# SH4_-_MICROCONTROLLER.net
KiCad netlist of a schematic drawn in Altium Designer
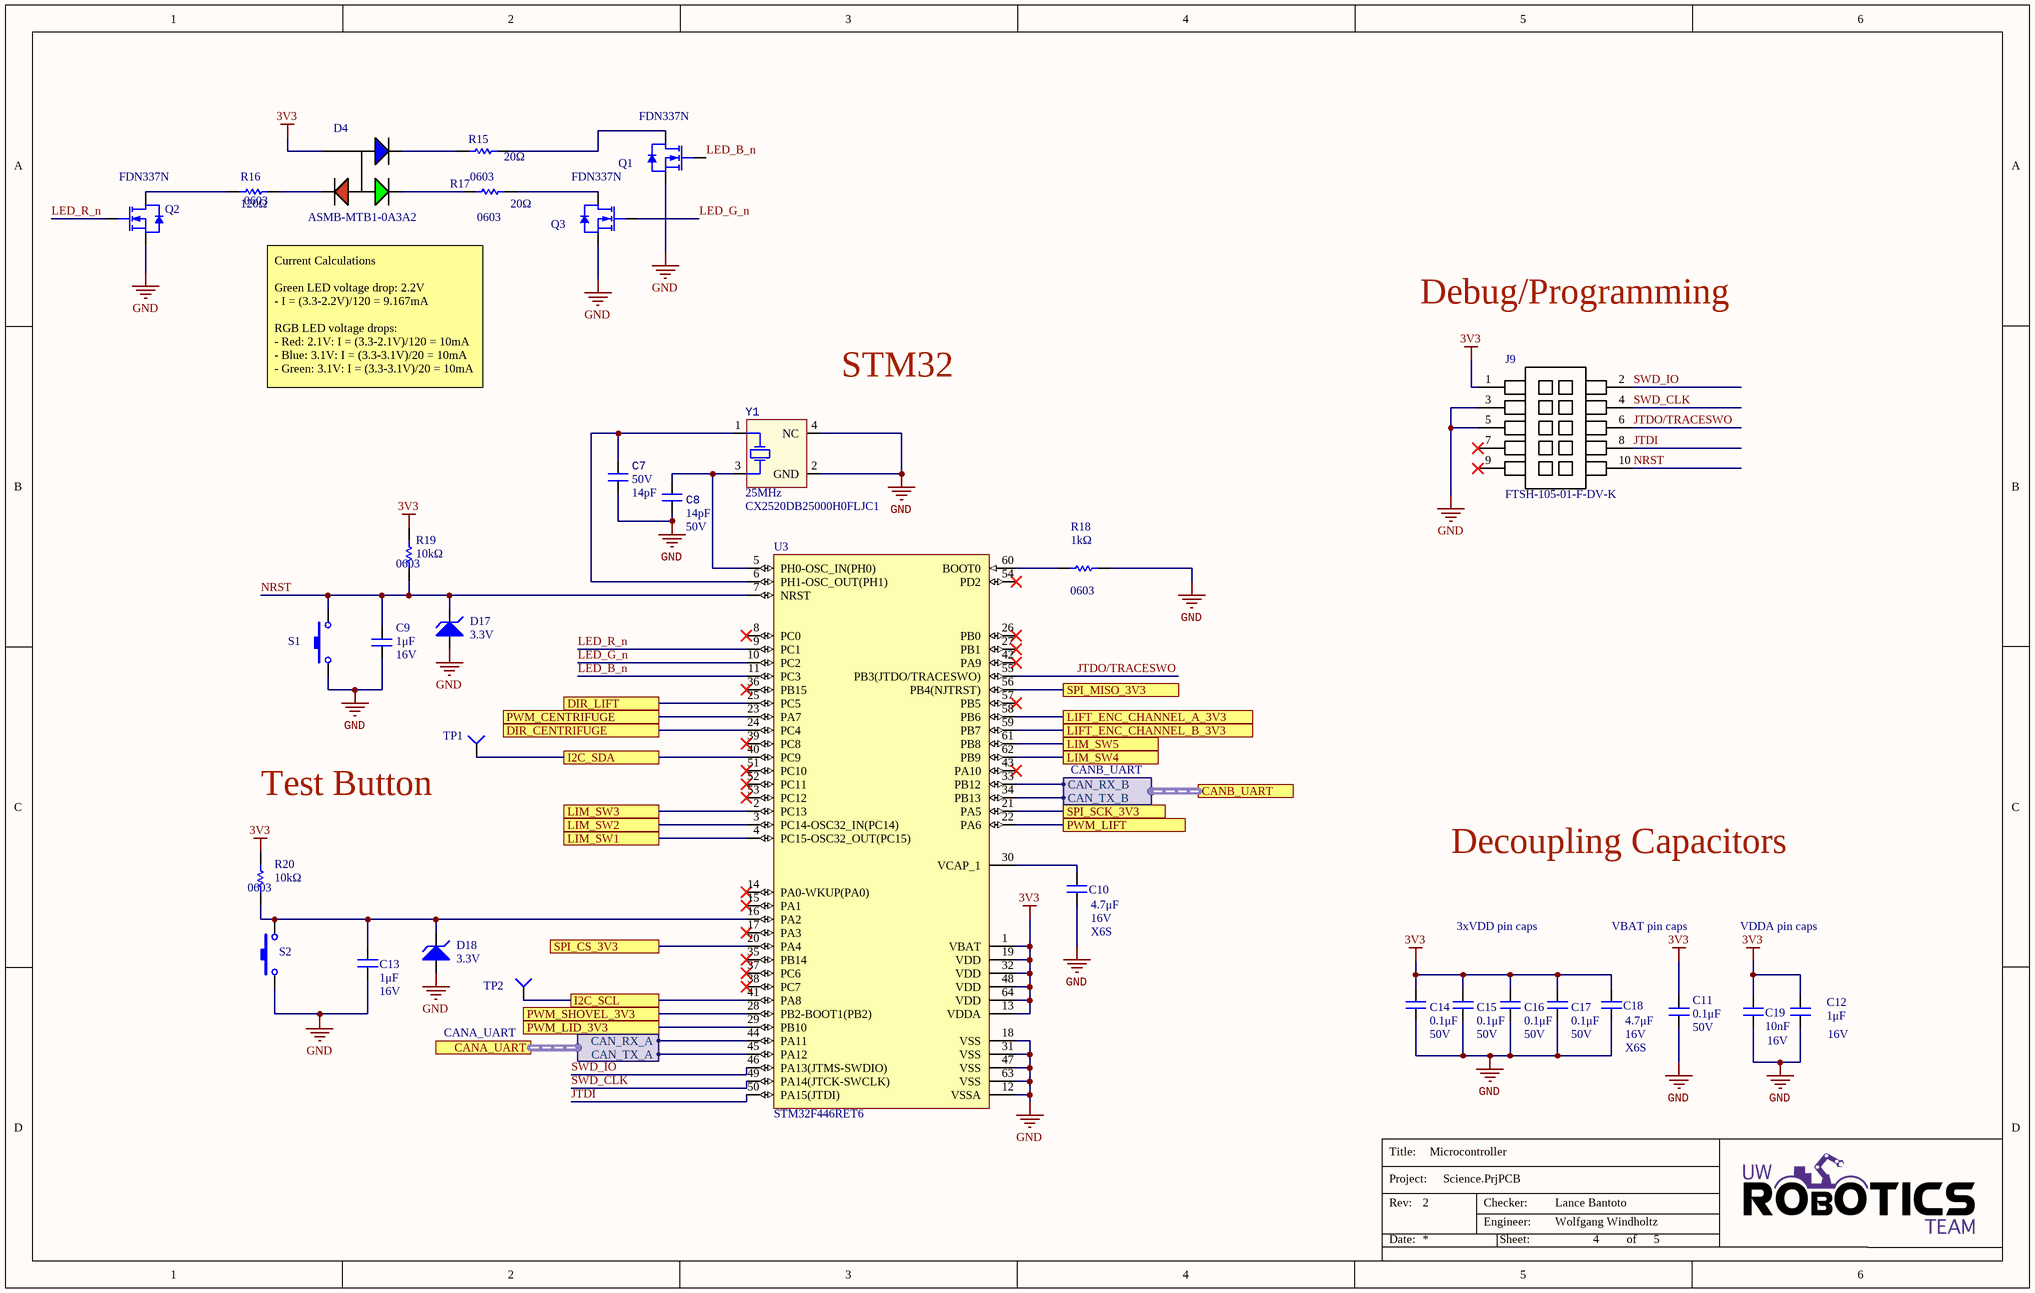
[diagram p0: SH4 - MICROCONTROLLER.SchDoc]

(export (version "E")
  (design (tool "Eeschema 10.0.6"))
  (components
    (comp (ref "C7")
      (value "14pF")
      (footprint "CAP0603")
      (description "CAP CER 14PF 50V C0G/NP0 0603")
      (fields (field (name "VOLTAGE RATING") "50V") (field (name "Comment") "CAP_14pF_50V_0603"))
      (libsource (lib "UWRT_Schematic_Library_2020") (part "CAP_14pF_50V_0603"))
    )
    (comp (ref "C8")
      (value "14pF")
      (footprint "CAP0603")
      (description "CAP CER 14PF 50V C0G/NP0 0603")
      (fields (field (name "VOLTAGE RATING") "50V") (field (name "Comment") "CAP_14pF_50V_0603"))
      (libsource (lib "UWRT_Schematic_Library_2020") (part "CAP_14pF_50V_0603"))
    )
    (comp (ref "C9")
      (value "1μF")
      (footprint "CAP0603")
      (description "CAP CER 1UF 16V Y5V 0603")
      (fields
        (field (name "VOLTAGE RATING") "16V")
        (field (name "MANUFACTURER PART NUMBER") "CC0603ZRY5V7BB105")
        (field (name "Comment") "CAP_1uF_16V_0603")
      )
      (libsource (lib "UWRT_Schematic_Library_2020") (part "CAP_1uF_16V_0603"))
    )
    (comp (ref "C10")
      (value "4.7μF")
      (footprint "CAP0603")
      (description "CAP CER 4.7UF 16V X6S 0603")
      (fields
        (field (name "DIELECTRIC") "X6S")
        (field (name "VOLTAGE RATING") "16V")
        (field (name "Comment") "CAP_4.7uF_16V_0603")
      )
      (libsource (lib "UWRT_Schematic_Library_2020") (part "CAP_4.7uF_16V_0603"))
    )
    (comp (ref "C11")
      (value "0.1μF")
      (footprint "CAP0603")
      (description "CAP CER 0.1UF 50V X7R 0603")
      (fields (field (name "VOLTAGE RATING") "50V") (field (name "Comment") "CAP_0.1uF_50V_0603"))
      (libsource (lib "UWRT_Schematic_Library_2020") (part "CAP_0.1uF_50V_0603"))
    )
    (comp (ref "C12")
      (value "1μF")
      (footprint "CAP0603")
      (description "CAP CER 1UF 16V Y5V 0603")
      (fields
        (field (name "VOLTAGE RATING") "16V")
        (field (name "MANUFACTURER PART NUMBER") "CC0603ZRY5V7BB105")
        (field (name "Comment") "CAP_1uF_16V_0603")
      )
      (libsource (lib "UWRT_Schematic_Library_2020") (part "CAP_1uF_16V_0603"))
    )
    (comp (ref "C13")
      (value "1μF")
      (footprint "CAP0603")
      (description "CAP CER 1UF 16V Y5V 0603")
      (fields
        (field (name "VOLTAGE RATING") "16V")
        (field (name "MANUFACTURER PART NUMBER") "CC0603ZRY5V7BB105")
        (field (name "Comment") "CAP_1uF_16V_0603")
      )
      (libsource (lib "UWRT_Schematic_Library_2020") (part "CAP_1uF_16V_0603"))
    )
    (comp (ref "C14")
      (value "0.1μF")
      (footprint "CAP0603")
      (description "CAP CER 0.1UF 50V X7R 0603")
      (fields (field (name "VOLTAGE RATING") "50V") (field (name "Comment") "CAP_0.1uF_50V_0603"))
      (libsource (lib "UWRT_Schematic_Library_2020") (part "CAP_0.1uF_50V_0603"))
    )
    (comp (ref "C15")
      (value "0.1μF")
      (footprint "CAP0603")
      (description "CAP CER 0.1UF 50V X7R 0603")
      (fields (field (name "VOLTAGE RATING") "50V") (field (name "Comment") "CAP_0.1uF_50V_0603"))
      (libsource (lib "UWRT_Schematic_Library_2020") (part "CAP_0.1uF_50V_0603"))
    )
    (comp (ref "C16")
      (value "0.1μF")
      (footprint "CAP0603")
      (description "CAP CER 0.1UF 50V X7R 0603")
      (fields (field (name "VOLTAGE RATING") "50V") (field (name "Comment") "CAP_0.1uF_50V_0603"))
      (libsource (lib "UWRT_Schematic_Library_2020") (part "CAP_0.1uF_50V_0603"))
    )
    (comp (ref "C17")
      (value "0.1μF")
      (footprint "CAP0603")
      (description "CAP CER 0.1UF 50V X7R 0603")
      (fields (field (name "VOLTAGE RATING") "50V") (field (name "Comment") "CAP_0.1uF_50V_0603"))
      (libsource (lib "UWRT_Schematic_Library_2020") (part "CAP_0.1uF_50V_0603"))
    )
    (comp (ref "C18")
      (value "4.7μF")
      (footprint "CAP0603")
      (description "CAP CER 4.7UF 16V X6S 0603")
      (fields
        (field (name "DIELECTRIC") "X6S")
        (field (name "VOLTAGE RATING") "16V")
        (field (name "Comment") "CAP_4.7uF_16V_0603")
      )
      (libsource (lib "UWRT_Schematic_Library_2020") (part "CAP_4.7uF_16V_0603"))
    )
    (comp (ref "C19")
      (value "10nF")
      (footprint "CAP0603")
      (description "CAP CER 10000PF 16V X7R 0603")
      (fields (field (name "VOLTAGE RATING") "16V") (field (name "Comment") "CAP_10nF_0603"))
      (libsource (lib "UWRT_Schematic_Library_2020") (part "CAP_10nF_0603"))
    )
    (comp (ref "D4")
      (value "LED_RGB")
      (footprint "LED_RGB")
      (description "LED RGB DIFFUSED 4PLCC SMD")
      (fields (field (name "MANUFACTURER PART NUMBER 1") "ASMB-MTB1-0A3A2"))
      (libsource (lib "UWRT_Schematic_Library_2020") (part "LED_RGB"))
    )
    (comp (ref "D17")
      (value "ESD5Z3.3T1G")
      (footprint "SOD523_UNI")
      (description "TVS DIODE 3.3V 14.1V SOD523")
      (fields (field (name "REVERSE STANDOFF VOLTAGE") "3.3V"))
      (libsource (lib "UWRT_Schematic_Library_2020") (part "ESD5Z3.3T1G"))
    )
    (comp (ref "D18")
      (value "ESD5Z3.3T1G")
      (footprint "SOD523_UNI")
      (description "TVS DIODE 3.3V 14.1V SOD523")
      (fields (field (name "REVERSE STANDOFF VOLTAGE") "3.3V"))
      (libsource (lib "UWRT_Schematic_Library_2020") (part "ESD5Z3.3T1G"))
    )
    (comp (ref "J9")
      (value "CON_PROGRAMMING")
      (footprint "FTSH-105-01-F-DV-K-P-TR")
      (description "CONN HEADER SMD 10POS 1.27MM")
      (fields (field (name "MANUFACTURER PART NUMBER 1") "FTSH-105-01-F-DV-K"))
      (libsource (lib "UWRT_Schematic_Library_2020") (part "CON_PROGRAMMING"))
    )
    (comp (ref "Q1")
      (value "NMOS_30V_2.2A")
      (footprint "NMOS_SSOT-3")
      (description "MOSFET N-CH 30V 2.2A SUPERSOT3")
      (fields (field (name "MANUFACTURER PART NUMBER 1") "FDN337N"))
      (libsource (lib "UWRT_Schematic_Library_2020") (part "NMOS_30V_2.2A"))
    )
    (comp (ref "Q2")
      (value "NMOS_30V_2.2A")
      (footprint "NMOS_SSOT-3")
      (description "MOSFET N-CH 30V 2.2A SUPERSOT3")
      (fields (field (name "MANUFACTURER PART NUMBER 1") "FDN337N"))
      (libsource (lib "UWRT_Schematic_Library_2020") (part "NMOS_30V_2.2A"))
    )
    (comp (ref "Q3")
      (value "NMOS_30V_2.2A")
      (footprint "NMOS_SSOT-3")
      (description "MOSFET N-CH 30V 2.2A SUPERSOT3")
      (fields (field (name "MANUFACTURER PART NUMBER 1") "FDN337N"))
      (libsource (lib "UWRT_Schematic_Library_2020") (part "NMOS_30V_2.2A"))
    )
    (comp (ref "R15")
      (value "20Ω")
      (footprint "RESC0603")
      (description "RES 20 OHM 5% 1/10W 0603")
      (fields
        (field (name "TOLERANCE") "5%")
        (field (name "PACKAGE/FOOTPRINT") "0603")
        (field (name "Comment") "RES_20Ω_0603_5%")
      )
      (libsource (lib "UWRT_Schematic_Library_2020") (part "RES_20Ω_0603_5%"))
    )
    (comp (ref "R16")
      (value "120Ω")
      (footprint "RESC0603")
      (description "RES 120 OHM 5% 1/10W 0603")
      (fields (field (name "PACKAGE/FOOTPRINT") "0603") (field (name "Comment") "RES_120Ω_0603"))
      (libsource (lib "UWRT_Schematic_Library_2020") (part "RES_120Ω_0603_5%"))
    )
    (comp (ref "R17")
      (value "20Ω")
      (footprint "RESC0603")
      (description "RES 20 OHM 5% 1/10W 0603")
      (fields
        (field (name "TOLERANCE") "5%")
        (field (name "PACKAGE/FOOTPRINT") "0603")
        (field (name "Comment") "RES_20Ω_0603_5%")
      )
      (libsource (lib "UWRT_Schematic_Library_2020") (part "RES_20Ω_0603_5%"))
    )
    (comp (ref "R18")
      (value "1kΩ")
      (footprint "RESC0603")
      (description "RES 1K OHM 5% 1/10W 0603")
      (fields
        (field (name "TOLERANCE") "5%")
        (field (name "PACKAGE/FOOTPRINT") "0603")
        (field (name "Comment") "RES_1kΩ_0603_5%")
      )
      (libsource (lib "UWRT_Schematic_Library_2020") (part "RES_1kΩ_0603_5%"))
    )
    (comp (ref "R19")
      (value "10kΩ")
      (footprint "RESC0603")
      (description "RES 10K OHM 5% 1/10W 0603")
      (fields
        (field (name "TOLERANCE") "5%")
        (field (name "PACKAGE/FOOTPRINT") "0603")
        (field (name "Comment") "RES_10kΩ_0603_5%")
      )
      (libsource (lib "UWRT_Schematic_Library_2020") (part "RES_10kΩ_0603_5%"))
    )
    (comp (ref "R20")
      (value "10kΩ")
      (footprint "RESC0603")
      (description "RES 10K OHM 5% 1/10W 0603")
      (fields
        (field (name "TOLERANCE") "5%")
        (field (name "PACKAGE/FOOTPRINT") "0603")
        (field (name "Comment") "RES_10kΩ_0603_5%")
      )
      (libsource (lib "UWRT_Schematic_Library_2020") (part "RES_10kΩ_0603_5%"))
    )
    (comp (ref "S1")
      (value "SW_TACTILE")
      (footprint "B3U-1000P")
      (description "SWITCH TACTILE SPST-NO 0.05A 12V")
      (libsource (lib "UWRT_Schematic_Library_2020") (part "SW_TACTILE"))
    )
    (comp (ref "S2")
      (value "SW_TACTILE")
      (footprint "B3U-1000P")
      (description "SWITCH TACTILE SPST-NO 0.05A 12V")
      (libsource (lib "UWRT_Schematic_Library_2020") (part "SW_TACTILE"))
    )
    (comp (ref "TP1")
      (value "TESTPOINT_1MM_CIRCLE")
      (footprint "TESTPOINT_CIRCLE_1MM")
      (description "TESTPOINT 1MM CIRCLE")
      (libsource (lib "UWRT_Schematic_Library_2020") (part "TESTPOINT_1MM_CIRCLE"))
    )
    (comp (ref "TP2")
      (value "TESTPOINT_1MM_CIRCLE")
      (footprint "TESTPOINT_CIRCLE_1MM")
      (description "TESTPOINT 1MM CIRCLE")
      (libsource (lib "UWRT_Schematic_Library_2020") (part "TESTPOINT_1MM_CIRCLE"))
    )
    (comp (ref "U3")
      (value "STM32F446RET6")
      (footprint "STM-LQFP64_L")
      (libsource (lib "UWRT_Schematic_Library_2020") (part "MCU_STM32F446RET6"))
    )
    (comp (ref "Y1")
      (value "CRYSTAL_25MHZ")
      (footprint "SOIC254P1016X440-4N")
      (description "CRYSTAL 25.0000MHZ 12PF SMD")
      (fields
        (field (name "FREQUENCY") "25MHz")
        (field (name "MANUFACTURER PART NUMBER 1") "CX2520DB25000H0FLJC1")
      )
      (libsource (lib "UWRT_Schematic_Library_2020") (part "CRYSTAL_25MHZ"))
    )
  )
  (nets
    (net (code "3") (name "/CAN_RX_A") (class "Default")
      (node (ref "U3") (pin "44") (pinfunction "PA11_44") (pintype "bidirectional"))
    )
    (net (code "4") (name "/CAN_RX_B") (class "Default")
      (node (ref "U3") (pin "33") (pinfunction "PB12_33") (pintype "bidirectional"))
    )
    (net (code "5") (name "/CAN_TX_A") (class "Default")
      (node (ref "U3") (pin "45") (pinfunction "PA12_45") (pintype "bidirectional"))
    )
    (net (code "6") (name "/CAN_TX_B") (class "Default")
      (node (ref "U3") (pin "34") (pinfunction "PB13_34") (pintype "bidirectional"))
    )
    (net (code "7") (name "/DIR_CENTRIFUGE") (class "Default")
      (node (ref "U3") (pin "24") (pinfunction "PC4_24") (pintype "bidirectional"))
    )
    (net (code "8") (name "/DIR_LIFT") (class "Default")
      (node (ref "U3") (pin "25") (pinfunction "PC5_25") (pintype "bidirectional"))
    )
    (net (code "9") (name "/I2C_SCL") (class "Default")
      (node (ref "TP2") (pin "1") (pinfunction "=value_1") (pintype "passive"))
      (node (ref "U3") (pin "41") (pinfunction "PA8_41") (pintype "bidirectional"))
    )
    (net (code "10") (name "/I2C_SDA") (class "Default")
      (node (ref "TP1") (pin "1") (pinfunction "=value_1") (pintype "passive"))
      (node (ref "U3") (pin "40") (pinfunction "PC9_40") (pintype "bidirectional"))
    )
    (net (code "11") (name "/JTDI") (class "Default")
      (node (ref "J9") (pin "8") (pinfunction "8_8") (pintype "passive"))
      (node (ref "U3") (pin "50") (pinfunction "PA15(JTDI)_50") (pintype "bidirectional"))
    )
    (net (code "12") (name "/JTDO{slash}TRACESWO") (class "Default")
      (node (ref "J9") (pin "6") (pinfunction "6_6") (pintype "passive"))
      (node (ref "U3") (pin "55") (pinfunction "PB3(JTDO/TRACESWO)_55") (pintype "bidirectional"))
    )
    (net (code "13") (name "/LED_B_n") (class "Default")
      (node (ref "Q1") (pin "1") (pinfunction "GATE_1") (pintype "passive"))
      (node (ref "U3") (pin "11") (pinfunction "PC3_11") (pintype "bidirectional"))
    )
    (net (code "14") (name "/LED_G_n") (class "Default")
      (node (ref "Q3") (pin "1") (pinfunction "GATE_1") (pintype "passive"))
      (node (ref "U3") (pin "10") (pinfunction "PC2_10") (pintype "bidirectional"))
    )
    (net (code "15") (name "/LED_R_n") (class "Default")
      (node (ref "Q2") (pin "1") (pinfunction "GATE_1") (pintype "passive"))
      (node (ref "U3") (pin "9") (pinfunction "PC1_9") (pintype "bidirectional"))
    )
    (net (code "16") (name "/LIFT_ENC_CHANNEL_A_3V3") (class "Default")
      (node (ref "U3") (pin "58") (pinfunction "PB6_58") (pintype "bidirectional"))
    )
    (net (code "17") (name "/LIFT_ENC_CHANNEL_B_3V3") (class "Default")
      (node (ref "U3") (pin "59") (pinfunction "PB7_59") (pintype "bidirectional"))
    )
    (net (code "18") (name "/LIM_SW1") (class "Default")
      (node (ref "U3") (pin "4") (pinfunction "PC15-OSC32_OUT(PC15)_4") (pintype "bidirectional"))
    )
    (net (code "19") (name "/LIM_SW2") (class "Default")
      (node (ref "U3") (pin "3") (pinfunction "PC14-OSC32_IN(PC14)_3") (pintype "bidirectional"))
    )
    (net (code "20") (name "/LIM_SW3") (class "Default")
      (node (ref "U3") (pin "2") (pinfunction "PC13_2") (pintype "bidirectional"))
    )
    (net (code "21") (name "/LIM_SW4") (class "Default")
      (node (ref "U3") (pin "62") (pinfunction "PB9_62") (pintype "bidirectional"))
    )
    (net (code "22") (name "/LIM_SW5") (class "Default")
      (node (ref "U3") (pin "61") (pinfunction "PB8_61") (pintype "bidirectional"))
    )
    (net (code "23") (name "/NRST") (class "Default")
      (node (ref "C9") (pin "2") (pinfunction "2_2") (pintype "passive"))
      (node (ref "D17") (pin "2") (pinfunction "Cathode_2") (pintype "passive"))
      (node (ref "J9") (pin "10") (pinfunction "10_10") (pintype "passive"))
      (node (ref "R19") (pin "1") (pinfunction "1_1") (pintype "passive"))
      (node (ref "S1") (pin "1") (pinfunction "1_1") (pintype "passive"))
      (node (ref "U3") (pin "7") (pinfunction "NRST_7") (pintype "bidirectional"))
    )
    (net (code "24") (name "/PWM_CENTRIFUGE") (class "Default")
      (node (ref "U3") (pin "23") (pinfunction "PA7_23") (pintype "bidirectional"))
    )
    (net (code "25") (name "/PWM_LID_3V3") (class "Default")
      (node (ref "U3") (pin "29") (pinfunction "PB10_29") (pintype "bidirectional"))
    )
    (net (code "26") (name "/PWM_LIFT") (class "Default")
      (node (ref "U3") (pin "22") (pinfunction "PA6_22") (pintype "bidirectional"))
    )
    (net (code "27") (name "/PWM_SHOVEL_3V3") (class "Default")
      (node (ref "U3") (pin "28") (pinfunction "PB2-BOOT1(PB2)_28") (pintype "bidirectional"))
    )
    (net (code "28") (name "/SPI_CS_3V3") (class "Default")
      (node (ref "U3") (pin "20") (pinfunction "PA4_20") (pintype "bidirectional"))
    )
    (net (code "29") (name "/SPI_MISO_3V3") (class "Default")
      (node (ref "U3") (pin "56") (pinfunction "PB4(NJTRST)_56") (pintype "bidirectional"))
    )
    (net (code "30") (name "/SPI_SCK_3V3") (class "Default")
      (node (ref "U3") (pin "21") (pinfunction "PA5_21") (pintype "bidirectional"))
    )
    (net (code "31") (name "/SWD_CLK") (class "Default")
      (node (ref "J9") (pin "4") (pinfunction "4_4") (pintype "passive"))
      (node (ref "U3") (pin "49") (pinfunction "PA14(JTCK-SWCLK)_49") (pintype "bidirectional"))
    )
    (net (code "32") (name "/SWD_IO") (class "Default")
      (node (ref "J9") (pin "2") (pinfunction "2_2") (pintype "passive"))
      (node (ref "U3") (pin "46") (pinfunction "PA13(JTMS-SWDIO)_46") (pintype "bidirectional"))
    )
    (net (code "35") (name "3V3") (class "Default")
      (node (ref "C11") (pin "2") (pinfunction "2_2") (pintype "passive"))
      (node (ref "C12") (pin "2") (pinfunction "2_2") (pintype "passive"))
      (node (ref "C14") (pin "2") (pinfunction "2_2") (pintype "passive"))
      (node (ref "C15") (pin "2") (pinfunction "2_2") (pintype "passive"))
      (node (ref "C16") (pin "2") (pinfunction "2_2") (pintype "passive"))
      (node (ref "C17") (pin "2") (pinfunction "2_2") (pintype "passive"))
      (node (ref "C18") (pin "2") (pinfunction "2_2") (pintype "passive"))
      (node (ref "C19") (pin "2") (pinfunction "2_2") (pintype "passive"))
      (node (ref "D4") (pin "4") (pinfunction "COMMON_ANODE_4") (pintype "passive"))
      (node (ref "J9") (pin "1") (pinfunction "1_1") (pintype "passive"))
      (node (ref "R19") (pin "2") (pinfunction "2_2") (pintype "passive"))
      (node (ref "R20") (pin "2") (pinfunction "2_2") (pintype "passive"))
      (node (ref "U3") (pin "1") (pinfunction "VBAT_1") (pintype "power_in"))
      (node (ref "U3") (pin "13") (pinfunction "VDDA_13") (pintype "power_in"))
      (node (ref "U3") (pin "19") (pinfunction "VDD_19") (pintype "power_in"))
      (node (ref "U3") (pin "32") (pinfunction "VDD_32") (pintype "power_in"))
      (node (ref "U3") (pin "48") (pinfunction "VDD_48") (pintype "power_in"))
      (node (ref "U3") (pin "64") (pinfunction "VDD_64") (pintype "power_in"))
    )
    (net (code "36") (name "GND") (class "Default")
      (node (ref "C10") (pin "1") (pinfunction "1_1") (pintype "passive"))
      (node (ref "C11") (pin "1") (pinfunction "1_1") (pintype "passive"))
      (node (ref "C12") (pin "1") (pinfunction "1_1") (pintype "passive"))
      (node (ref "C13") (pin "1") (pinfunction "1_1") (pintype "passive"))
      (node (ref "C14") (pin "1") (pinfunction "1_1") (pintype "passive"))
      (node (ref "C15") (pin "1") (pinfunction "1_1") (pintype "passive"))
      (node (ref "C16") (pin "1") (pinfunction "1_1") (pintype "passive"))
      (node (ref "C17") (pin "1") (pinfunction "1_1") (pintype "passive"))
      (node (ref "C18") (pin "1") (pinfunction "1_1") (pintype "passive"))
      (node (ref "C19") (pin "1") (pinfunction "1_1") (pintype "passive"))
      (node (ref "C7") (pin "1") (pinfunction "1_1") (pintype "passive"))
      (node (ref "C8") (pin "1") (pinfunction "1_1") (pintype "passive"))
      (node (ref "C9") (pin "1") (pinfunction "1_1") (pintype "passive"))
      (node (ref "D17") (pin "1") (pinfunction "Anode_1") (pintype "passive"))
      (node (ref "D18") (pin "1") (pinfunction "Anode_1") (pintype "passive"))
      (node (ref "J9") (pin "3") (pinfunction "3_3") (pintype "passive"))
      (node (ref "J9") (pin "5") (pinfunction "5_5") (pintype "passive"))
      (node (ref "Q1") (pin "2") (pinfunction "SOURCE_2") (pintype "passive"))
      (node (ref "Q2") (pin "2") (pinfunction "SOURCE_2") (pintype "passive"))
      (node (ref "Q3") (pin "2") (pinfunction "SOURCE_2") (pintype "passive"))
      (node (ref "R18") (pin "2") (pinfunction "2_2") (pintype "passive"))
      (node (ref "S1") (pin "2") (pinfunction "2_2") (pintype "passive"))
      (node (ref "S2") (pin "1") (pinfunction "1_1") (pintype "passive"))
      (node (ref "U3") (pin "12") (pinfunction "VSSA_12") (pintype "power_in"))
      (node (ref "U3") (pin "18") (pinfunction "VSS_18") (pintype "power_in"))
      (node (ref "U3") (pin "31") (pinfunction "VSS_31") (pintype "power_in"))
      (node (ref "U3") (pin "47") (pinfunction "VSS_47") (pintype "power_in"))
      (node (ref "U3") (pin "63") (pinfunction "VSS_63") (pintype "power_in"))
      (node (ref "Y1") (pin "2") (pinfunction "GND_2") (pintype "power_in"))
      (node (ref "Y1") (pin "4") (pinfunction "NC_4") (pintype "passive"))
    )
    (net (code "37") (name "Net-(D4-CATHODE_(BLUE))") (class "Default")
      (node (ref "D4") (pin "3") (pinfunction "CATHODE_(BLUE)_3") (pintype "passive"))
      (node (ref "R15") (pin "1") (pinfunction "1_1") (pintype "passive"))
    )
    (net (code "38") (name "Net-(D4-CATHODE_(GREEN))") (class "Default")
      (node (ref "D4") (pin "2") (pinfunction "CATHODE_(GREEN)_2") (pintype "passive"))
      (node (ref "R17") (pin "1") (pinfunction "1_1") (pintype "passive"))
    )
    (net (code "39") (name "Net-(D4-CATHODE_(RED))") (class "Default")
      (node (ref "D4") (pin "1") (pinfunction "CATHODE_(RED)_1") (pintype "passive"))
      (node (ref "R16") (pin "2") (pinfunction "2_2") (pintype "passive"))
    )
    (net (code "40") (name "Net-(D18-Cathode)") (class "Default")
      (node (ref "C13") (pin "2") (pinfunction "2_2") (pintype "passive"))
      (node (ref "D18") (pin "2") (pinfunction "Cathode_2") (pintype "passive"))
      (node (ref "R20") (pin "1") (pinfunction "1_1") (pintype "passive"))
      (node (ref "S2") (pin "2") (pinfunction "2_2") (pintype "passive"))
      (node (ref "U3") (pin "16") (pinfunction "PA2_16") (pintype "bidirectional"))
    )
    (net (code "41") (name "Net-(Q1-DRAIN)") (class "Default")
      (node (ref "Q1") (pin "3") (pinfunction "DRAIN_3") (pintype "passive"))
      (node (ref "R15") (pin "2") (pinfunction "2_2") (pintype "passive"))
    )
    (net (code "42") (name "Net-(Q2-DRAIN)") (class "Default")
      (node (ref "Q2") (pin "3") (pinfunction "DRAIN_3") (pintype "passive"))
      (node (ref "R16") (pin "1") (pinfunction "1_1") (pintype "passive"))
    )
    (net (code "43") (name "Net-(Q3-DRAIN)") (class "Default")
      (node (ref "Q3") (pin "3") (pinfunction "DRAIN_3") (pintype "passive"))
      (node (ref "R17") (pin "2") (pinfunction "2_2") (pintype "passive"))
    )
    (net (code "44") (name "Net-(U3-BOOT0)") (class "Default")
      (node (ref "R18") (pin "1") (pinfunction "1_1") (pintype "passive"))
      (node (ref "U3") (pin "60") (pinfunction "BOOT0_60") (pintype "input"))
    )
    (net (code "45") (name "Net-(U3-PH0-OSC_IN(PH0))") (class "Default")
      (node (ref "C8") (pin "2") (pinfunction "2_2") (pintype "passive"))
      (node (ref "U3") (pin "5") (pinfunction "PH0-OSC_IN(PH0)_5") (pintype "bidirectional"))
      (node (ref "Y1") (pin "3") (pinfunction "HOT_3") (pintype "passive"))
    )
    (net (code "46") (name "Net-(U3-PH1-OSC_OUT(PH1))") (class "Default")
      (node (ref "C7") (pin "2") (pinfunction "2_2") (pintype "passive"))
      (node (ref "U3") (pin "6") (pinfunction "PH1-OSC_OUT(PH1)_6") (pintype "bidirectional"))
      (node (ref "Y1") (pin "1") (pinfunction "HOT_1") (pintype "passive"))
    )
    (net (code "47") (name "Net-(U3-VCAP_1)") (class "Default")
      (node (ref "C10") (pin "2") (pinfunction "2_2") (pintype "passive"))
      (node (ref "U3") (pin "30") (pinfunction "VCAP_1_30") (pintype "passive"))
    )
    (net (code "48") (name "unconnected-(J9-Pad7)") (class "Default")
      (node (ref "J9") (pin "7") (pinfunction "7_7") (pintype "passive+no_connect"))
    )
    (net (code "49") (name "unconnected-(J9-Pad9)") (class "Default")
      (node (ref "J9") (pin "9") (pinfunction "9_9") (pintype "passive+no_connect"))
    )
    (net (code "50") (name "unconnected-(U3-PA0-WKUP(PA0)-Pad14)") (class "Default")
      (node (ref "U3") (pin "14") (pinfunction "PA0-WKUP(PA0)_14") (pintype "bidirectional+no_connect"))
    )
    (net (code "51") (name "unconnected-(U3-PA1-Pad15)") (class "Default")
      (node (ref "U3") (pin "15") (pinfunction "PA1_15") (pintype "bidirectional+no_connect"))
    )
    (net (code "52") (name "unconnected-(U3-PA3-Pad17)") (class "Default")
      (node (ref "U3") (pin "17") (pinfunction "PA3_17") (pintype "bidirectional+no_connect"))
    )
    (net (code "53") (name "unconnected-(U3-PA9-Pad42)") (class "Default")
      (node (ref "U3") (pin "42") (pinfunction "PA9_42") (pintype "bidirectional+no_connect"))
    )
    (net (code "54") (name "unconnected-(U3-PA10-Pad43)") (class "Default")
      (node (ref "U3") (pin "43") (pinfunction "PA10_43") (pintype "bidirectional+no_connect"))
    )
    (net (code "55") (name "unconnected-(U3-PB0-Pad26)") (class "Default")
      (node (ref "U3") (pin "26") (pinfunction "PB0_26") (pintype "bidirectional+no_connect"))
    )
    (net (code "56") (name "unconnected-(U3-PB1-Pad27)") (class "Default")
      (node (ref "U3") (pin "27") (pinfunction "PB1_27") (pintype "bidirectional+no_connect"))
    )
    (net (code "57") (name "unconnected-(U3-PB5-Pad57)") (class "Default")
      (node (ref "U3") (pin "57") (pinfunction "PB5_57") (pintype "bidirectional+no_connect"))
    )
    (net (code "58") (name "unconnected-(U3-PB14-Pad35)") (class "Default")
      (node (ref "U3") (pin "35") (pinfunction "PB14_35") (pintype "bidirectional+no_connect"))
    )
    (net (code "59") (name "unconnected-(U3-PB15-Pad36)") (class "Default")
      (node (ref "U3") (pin "36") (pinfunction "PB15_36") (pintype "bidirectional+no_connect"))
    )
    (net (code "60") (name "unconnected-(U3-PC0-Pad8)") (class "Default")
      (node (ref "U3") (pin "8") (pinfunction "PC0_8") (pintype "bidirectional+no_connect"))
    )
    (net (code "61") (name "unconnected-(U3-PC6-Pad37)") (class "Default")
      (node (ref "U3") (pin "37") (pinfunction "PC6_37") (pintype "bidirectional+no_connect"))
    )
    (net (code "62") (name "unconnected-(U3-PC7-Pad38)") (class "Default")
      (node (ref "U3") (pin "38") (pinfunction "PC7_38") (pintype "bidirectional+no_connect"))
    )
    (net (code "63") (name "unconnected-(U3-PC8-Pad39)") (class "Default")
      (node (ref "U3") (pin "39") (pinfunction "PC8_39") (pintype "bidirectional+no_connect"))
    )
    (net (code "64") (name "unconnected-(U3-PC10-Pad51)") (class "Default")
      (node (ref "U3") (pin "51") (pinfunction "PC10_51") (pintype "bidirectional+no_connect"))
    )
    (net (code "65") (name "unconnected-(U3-PC11-Pad52)") (class "Default")
      (node (ref "U3") (pin "52") (pinfunction "PC11_52") (pintype "bidirectional+no_connect"))
    )
    (net (code "66") (name "unconnected-(U3-PC12-Pad53)") (class "Default")
      (node (ref "U3") (pin "53") (pinfunction "PC12_53") (pintype "bidirectional+no_connect"))
    )
    (net (code "67") (name "unconnected-(U3-PD2-Pad54)") (class "Default")
      (node (ref "U3") (pin "54") (pinfunction "PD2_54") (pintype "bidirectional+no_connect"))
    )
  )
)
